# GPS_L80.net
KiCad netlist of a schematic drawn in Altium Designer
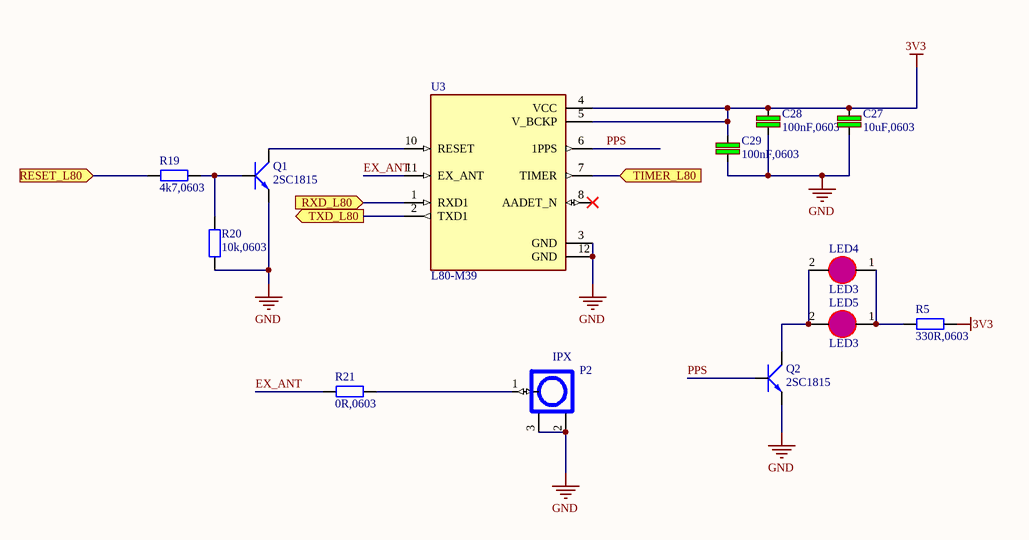
[diagram p0: GPS_L80.SchDoc]

(export (version "E")
  (design (tool "Eeschema 10.0.6"))
  (components
    (comp (ref "C27")
      (value "10uF,0603")
      (footprint "CAP_0603")
      (description "4.7µF ±10% 35V Ceramic Capacitor X5R 0805 (2012 Metric)")
      (fields
        (field (name "MANUFACTURER") "Samsung Electro-Mechanics")
        (field (name "PART NUMBER") "CL21A475KLCLQNC")
      )
      (libsource (lib "Anh_Trung") (part "C"))
    )
    (comp (ref "C28")
      (value "100nF,0603")
      (footprint "CAP_0603")
      (description "4.7µF ±10% 35V Ceramic Capacitor X5R 0805 (2012 Metric)")
      (fields
        (field (name "MANUFACTURER") "Samsung Electro-Mechanics")
        (field (name "PART NUMBER") "CL21A475KLCLQNC")
      )
      (libsource (lib "Anh_Trung") (part "C"))
    )
    (comp (ref "C29")
      (value "100nF,0603")
      (footprint "CAP_0603")
      (description "4.7µF ±10% 35V Ceramic Capacitor X5R 0805 (2012 Metric)")
      (fields
        (field (name "MANUFACTURER") "Samsung Electro-Mechanics")
        (field (name "PART NUMBER") "CL21A475KLCLQNC")
      )
      (libsource (lib "Anh_Trung") (part "C"))
    )
    (comp (ref "LED4")
      (value "LED3")
      (footprint "LED0805")
      (description "LED SMD 0805")
      (libsource (lib "My Library 2") (part "LED0805"))
    )
    (comp (ref "LED5")
      (value "LED3")
      (footprint "LED0805")
      (description "LED SMD 0805")
      (libsource (lib "My Library 2") (part "LED0805"))
    )
    (comp (ref "P2")
      (value "IPX")
      (footprint "IPXS")
      (description "Antenna GSM GPS")
      (fields
        (field (name "MANUFACTURER") "TE Connectivity AMP Connectors")
        (field (name "PART NUMBER") "2334884-1")
      )
      (libsource (lib "Anh_Trung") (part "IPXSx66"))
    )
    (comp (ref "Q1")
      (value "2SC1815")
      (footprint "SOT23")
      (description "NPN 600mW, ECB")
      (libsource (lib "My Library 2") (part "2SC1815"))
    )
    (comp (ref "Q2")
      (value "2SC1815")
      (footprint "SOT23-321")
      (description "NPN 600mW, ECB")
      (libsource (lib "My Library 2") (part "2SC1815"))
    )
    (comp (ref "R5")
      (value "330R,0603")
      (footprint "RES-SMD-0603")
      (description "Resistor SMD")
      (fields
        (field (name "MANUFACTURER") "Generic Components")
        (field (name "PUBLISHER") "Altium Hobart Technology Centre")
      )
      (libsource (lib "My Library") (part "Resistor - SMD"))
    )
    (comp (ref "R19")
      (value "4k7,0603")
      (footprint "RES-SMD-0603")
      (description "Resistor SMD")
      (fields
        (field (name "MANUFACTURER") "Generic Components")
        (field (name "PUBLISHER") "Altium Hobart Technology Centre")
      )
      (libsource (lib "My Library") (part "Resistor - SMD"))
    )
    (comp (ref "R20")
      (value "10k,0603")
      (footprint "RES-SMD-0603")
      (description "Resistor SMD")
      (fields
        (field (name "MANUFACTURER") "Generic Components")
        (field (name "PUBLISHER") "Altium Hobart Technology Centre")
      )
      (libsource (lib "My Library") (part "Resistor - SMD"))
    )
    (comp (ref "R21")
      (value "0R,0603")
      (footprint "RES-SMD-0603")
      (description "Resistor SMD")
      (fields
        (field (name "MANUFACTURER") "Generic Components")
        (field (name "PUBLISHER") "Altium Hobart Technology Centre")
      )
      (libsource (lib "My Library") (part "Resistor - SMD"))
    )
    (comp (ref "U3")
      (value "L80-M39")
      (footprint "XCVR_L80-M39")
      (fields (field (name "MF") "Quectel"))
      (libsource (lib "L80-M39") (part "L80-M39"))
    )
  )
  (nets
    (net (code "1") (name "/EX_ANT") (class "Default")
      (node (ref "R21") (pin "2") (pinfunction "2_2") (pintype "passive"))
      (node (ref "U3") (pin "11") (pinfunction "EX_ANT_11") (pintype "input"))
    )
    (net (code "2") (name "/PPS") (class "Default")
      (node (ref "Q2") (pin "3") (pinfunction "B_3") (pintype "passive"))
      (node (ref "U3") (pin "6") (pinfunction "1PPS_6") (pintype "output"))
    )
    (net (code "3") (name "/RESET_L80") (class "Default")
      (node (ref "R19") (pin "2") (pinfunction "2_2") (pintype "passive"))
    )
    (net (code "4") (name "/RXD_L80") (class "Default")
      (node (ref "U3") (pin "1") (pinfunction "RXD1_1") (pintype "input"))
    )
    (net (code "5") (name "/TIMER_L80") (class "Default")
      (node (ref "U3") (pin "7") (pinfunction "TIMER_7") (pintype "output"))
    )
    (net (code "6") (name "/TXD_L80") (class "Default")
      (node (ref "U3") (pin "2") (pinfunction "TXD1_2") (pintype "output"))
    )
    (net (code "7") (name "3V3") (class "Default")
      (node (ref "C27") (pin "2") (pinfunction "2_2") (pintype "passive"))
      (node (ref "C28") (pin "2") (pinfunction "2_2") (pintype "passive"))
      (node (ref "C29") (pin "2") (pinfunction "2_2") (pintype "passive"))
      (node (ref "R5") (pin "1") (pinfunction "1_1") (pintype "passive"))
      (node (ref "U3") (pin "4") (pinfunction "VCC_4") (pintype "power_in"))
      (node (ref "U3") (pin "5") (pinfunction "V_BCKP_5") (pintype "power_in"))
    )
    (net (code "8") (name "GND") (class "Default")
      (node (ref "C27") (pin "1") (pinfunction "1_1") (pintype "passive"))
      (node (ref "C28") (pin "1") (pinfunction "1_1") (pintype "passive"))
      (node (ref "C29") (pin "1") (pinfunction "1_1") (pintype "passive"))
      (node (ref "P2") (pin "2") (pintype "passive"))
      (node (ref "P2") (pin "3") (pintype "passive"))
      (node (ref "Q1") (pin "1") (pinfunction "E_1") (pintype "passive"))
      (node (ref "Q2") (pin "1") (pinfunction "E_1") (pintype "passive"))
      (node (ref "R20") (pin "1") (pinfunction "1_1") (pintype "passive"))
      (node (ref "U3") (pin "12") (pinfunction "GND_12") (pintype "power_in"))
      (node (ref "U3") (pin "3") (pinfunction "GND_3") (pintype "power_in"))
    )
    (net (code "9") (name "Net-(LED4-A)") (class "Default")
      (node (ref "LED4") (pin "1") (pinfunction "A_1") (pintype "passive"))
      (node (ref "LED5") (pin "1") (pinfunction "A_1") (pintype "passive"))
      (node (ref "R5") (pin "2") (pinfunction "2_2") (pintype "passive"))
    )
    (net (code "10") (name "Net-(LED4-K)") (class "Default")
      (node (ref "LED4") (pin "2") (pinfunction "K_2") (pintype "passive"))
      (node (ref "LED5") (pin "2") (pinfunction "K_2") (pintype "passive"))
      (node (ref "Q2") (pin "2") (pinfunction "C_2") (pintype "passive"))
    )
    (net (code "11") (name "Net-(P2-Pad1)") (class "Default")
      (node (ref "P2") (pin "1") (pintype "bidirectional"))
      (node (ref "R21") (pin "1") (pinfunction "1_1") (pintype "passive"))
    )
    (net (code "12") (name "Net-(Q1-B)") (class "Default")
      (node (ref "Q1") (pin "3") (pinfunction "B_3") (pintype "passive"))
      (node (ref "R19") (pin "1") (pinfunction "1_1") (pintype "passive"))
      (node (ref "R20") (pin "2") (pinfunction "2_2") (pintype "passive"))
    )
    (net (code "13") (name "Net-(Q1-C)") (class "Default")
      (node (ref "Q1") (pin "2") (pinfunction "C_2") (pintype "passive"))
      (node (ref "U3") (pin "10") (pinfunction "RESET_10") (pintype "input"))
    )
    (net (code "14") (name "unconnected-(U3-AADET_N-Pad8)") (class "Default")
      (node (ref "U3") (pin "8") (pinfunction "AADET_N_8") (pintype "bidirectional+no_connect"))
    )
  )
)
